# 7-jack-sensor-board-nano.net
KiCad netlist of a schematic drawn in EAGLE
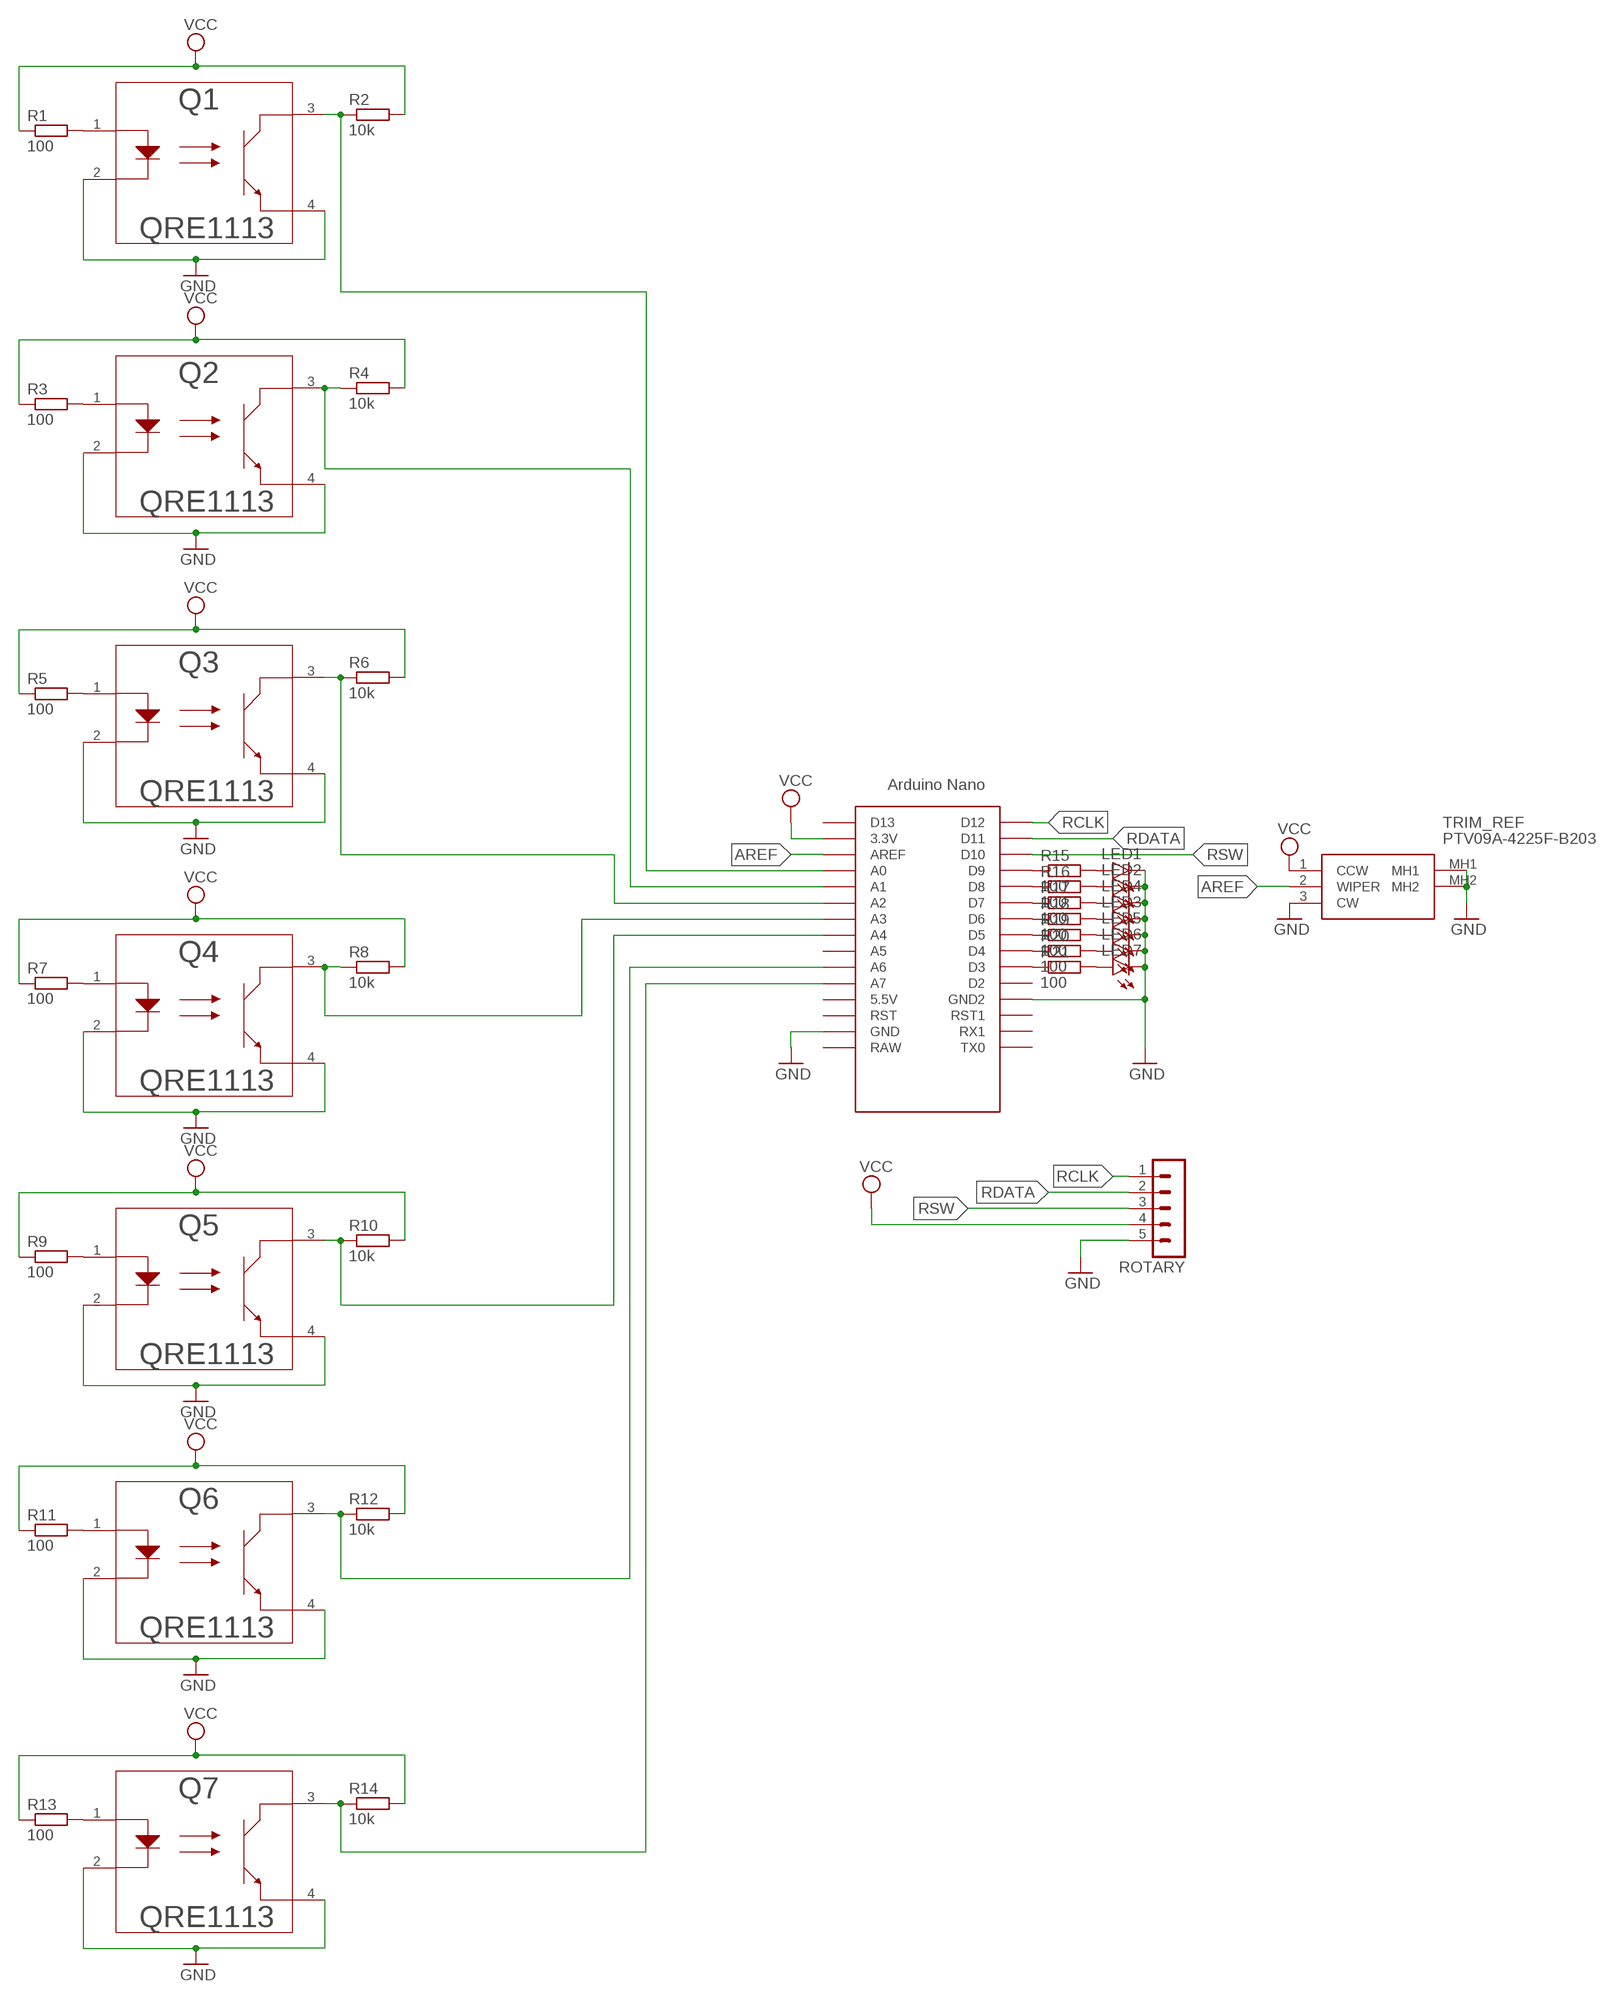
[diagram p0: schematic, sheet 1]

(export (version "E")
  (design (tool "Eeschema 10.0.6"))
  (components
    (comp (ref "LED1")
      (value "LED3MM")
      (footprint "eagle-import:LED3MM")
      (libsource (lib "eagle-import") (part "LED3MM"))
    )
    (comp (ref "LED2")
      (value "LED3MM")
      (footprint "eagle-import:LED3MM")
      (libsource (lib "eagle-import") (part "LED3MM"))
    )
    (comp (ref "LED3")
      (value "LED3MM")
      (footprint "eagle-import:LED3MM")
      (libsource (lib "eagle-import") (part "LED3MM"))
    )
    (comp (ref "LED4")
      (value "LED3MM")
      (footprint "eagle-import:LED3MM")
      (libsource (lib "eagle-import") (part "LED3MM"))
    )
    (comp (ref "LED5")
      (value "LED3MM")
      (footprint "eagle-import:LED3MM")
      (libsource (lib "eagle-import") (part "LED3MM"))
    )
    (comp (ref "LED6")
      (value "LED3MM")
      (footprint "eagle-import:LED3MM")
      (libsource (lib "eagle-import") (part "LED3MM"))
    )
    (comp (ref "LED7")
      (value "LED3MM")
      (footprint "eagle-import:LED3MM")
      (libsource (lib "eagle-import") (part "LED3MM"))
    )
    (comp (ref "Q1")
      (value "QRE1113")
      (footprint "eagle-import:DIP4_100AQ_ONS")
      (fields (field (name "COPYRIGHT") "Copyright (C) 2024 Ultra Librarian. All rights reserved."))
      (libsource (lib "eagle-import") (part "QRE1113"))
    )
    (comp (ref "Q2")
      (value "QRE1113")
      (footprint "eagle-import:DIP4_100AQ_ONS")
      (fields (field (name "COPYRIGHT") "Copyright (C) 2024 Ultra Librarian. All rights reserved."))
      (libsource (lib "eagle-import") (part "QRE1113"))
    )
    (comp (ref "Q3")
      (value "QRE1113")
      (footprint "eagle-import:DIP4_100AQ_ONS")
      (fields (field (name "COPYRIGHT") "Copyright (C) 2024 Ultra Librarian. All rights reserved."))
      (libsource (lib "eagle-import") (part "QRE1113"))
    )
    (comp (ref "Q4")
      (value "QRE1113")
      (footprint "eagle-import:DIP4_100AQ_ONS")
      (fields (field (name "COPYRIGHT") "Copyright (C) 2024 Ultra Librarian. All rights reserved."))
      (libsource (lib "eagle-import") (part "QRE1113"))
    )
    (comp (ref "Q5")
      (value "QRE1113")
      (footprint "eagle-import:DIP4_100AQ_ONS")
      (fields (field (name "COPYRIGHT") "Copyright (C) 2024 Ultra Librarian. All rights reserved."))
      (libsource (lib "eagle-import") (part "QRE1113"))
    )
    (comp (ref "Q6")
      (value "QRE1113")
      (footprint "eagle-import:DIP4_100AQ_ONS")
      (fields (field (name "COPYRIGHT") "Copyright (C) 2024 Ultra Librarian. All rights reserved."))
      (libsource (lib "eagle-import") (part "QRE1113"))
    )
    (comp (ref "Q7")
      (value "QRE1113")
      (footprint "eagle-import:DIP4_100AQ_ONS")
      (fields (field (name "COPYRIGHT") "Copyright (C) 2024 Ultra Librarian. All rights reserved."))
      (libsource (lib "eagle-import") (part "QRE1113"))
    )
    (comp (ref "R1")
      (value "100")
      (footprint "eagle-import:0207_10")
      (libsource (lib "eagle-import") (part "R-EU_0207/10"))
    )
    (comp (ref "R2")
      (value "10k")
      (footprint "eagle-import:0207_10")
      (libsource (lib "eagle-import") (part "R-EU_0207/10"))
    )
    (comp (ref "R3")
      (value "100")
      (footprint "eagle-import:0207_10")
      (libsource (lib "eagle-import") (part "R-EU_0207/10"))
    )
    (comp (ref "R4")
      (value "10k")
      (footprint "eagle-import:0207_10")
      (libsource (lib "eagle-import") (part "R-EU_0207/10"))
    )
    (comp (ref "R5")
      (value "100")
      (footprint "eagle-import:0207_10")
      (libsource (lib "eagle-import") (part "R-EU_0207/10"))
    )
    (comp (ref "R6")
      (value "10k")
      (footprint "eagle-import:0207_10")
      (libsource (lib "eagle-import") (part "R-EU_0207/10"))
    )
    (comp (ref "R7")
      (value "100")
      (footprint "eagle-import:0207_10")
      (libsource (lib "eagle-import") (part "R-EU_0207/10"))
    )
    (comp (ref "R8")
      (value "10k")
      (footprint "eagle-import:0207_10")
      (libsource (lib "eagle-import") (part "R-EU_0207/10"))
    )
    (comp (ref "R9")
      (value "100")
      (footprint "eagle-import:0207_10")
      (libsource (lib "eagle-import") (part "R-EU_0207/10"))
    )
    (comp (ref "R10")
      (value "10k")
      (footprint "eagle-import:0207_10")
      (libsource (lib "eagle-import") (part "R-EU_0207/10"))
    )
    (comp (ref "R11")
      (value "100")
      (footprint "eagle-import:0207_10")
      (libsource (lib "eagle-import") (part "R-EU_0207/10"))
    )
    (comp (ref "R12")
      (value "10k")
      (footprint "eagle-import:0207_10")
      (libsource (lib "eagle-import") (part "R-EU_0207/10"))
    )
    (comp (ref "R13")
      (value "100")
      (footprint "eagle-import:0207_10")
      (libsource (lib "eagle-import") (part "R-EU_0207/10"))
    )
    (comp (ref "R14")
      (value "10k")
      (footprint "eagle-import:0207_10")
      (libsource (lib "eagle-import") (part "R-EU_0207/10"))
    )
    (comp (ref "R15")
      (value "100")
      (footprint "eagle-import:0207_10")
      (libsource (lib "eagle-import") (part "R-EU_0207/10"))
    )
    (comp (ref "R16")
      (value "100")
      (footprint "eagle-import:0207_10")
      (libsource (lib "eagle-import") (part "R-EU_0207/10"))
    )
    (comp (ref "R17")
      (value "100")
      (footprint "eagle-import:0207_10")
      (libsource (lib "eagle-import") (part "R-EU_0207/10"))
    )
    (comp (ref "R18")
      (value "100")
      (footprint "eagle-import:0207_10")
      (libsource (lib "eagle-import") (part "R-EU_0207/10"))
    )
    (comp (ref "R19")
      (value "100")
      (footprint "eagle-import:0207_10")
      (libsource (lib "eagle-import") (part "R-EU_0207/10"))
    )
    (comp (ref "R20")
      (value "100")
      (footprint "eagle-import:0207_10")
      (libsource (lib "eagle-import") (part "R-EU_0207/10"))
    )
    (comp (ref "R21")
      (value "100")
      (footprint "eagle-import:0207_10")
      (libsource (lib "eagle-import") (part "R-EU_0207/10"))
    )
    (comp (ref "ROTARY")
      (value "MA05-1")
      (footprint "eagle-import:MA05-1")
      (libsource (lib "eagle-import") (part "MA05-1"))
    )
    (comp (ref "TRIM_REF")
      (value "PTV09A-4225F-B203")
      (footprint "eagle-import:PTV09A4225FB203")
      (fields (field (name "MOUSER_PART_NUMBER") "652-PTV09A-4225FB203"))
      (libsource (lib "eagle-import") (part "PTV09A-4225F-B203"))
    )
    (comp (ref "U$1")
      (value "NANO")
      (footprint "eagle-import:NANO")
      (libsource (lib "eagle-import") (part "NANO"))
    )
  )
  (nets
    (net (code "1") (name "AREF") (class "Default")
      (node (ref "TRIM_REF") (pin "2") (pinfunction "WIPER_2") (pintype "bidirectional"))
      (node (ref "U$1") (pin "AREF") (pinfunction "AREF_AREF") (pintype "bidirectional"))
    )
    (net (code "2") (name "GND") (class "Default")
      (node (ref "LED1") (pin "K") (pinfunction "C_K") (pintype "passive"))
      (node (ref "LED2") (pin "K") (pinfunction "C_K") (pintype "passive"))
      (node (ref "LED3") (pin "K") (pinfunction "C_K") (pintype "passive"))
      (node (ref "LED4") (pin "K") (pinfunction "C_K") (pintype "passive"))
      (node (ref "LED5") (pin "K") (pinfunction "C_K") (pintype "passive"))
      (node (ref "LED6") (pin "K") (pinfunction "C_K") (pintype "passive"))
      (node (ref "LED7") (pin "K") (pinfunction "C_K") (pintype "passive"))
      (node (ref "Q1") (pin "2") (pinfunction "2_2") (pintype "passive"))
      (node (ref "Q1") (pin "4") (pinfunction "4_4") (pintype "passive"))
      (node (ref "Q2") (pin "2") (pinfunction "2_2") (pintype "passive"))
      (node (ref "Q2") (pin "4") (pinfunction "4_4") (pintype "passive"))
      (node (ref "Q3") (pin "2") (pinfunction "2_2") (pintype "passive"))
      (node (ref "Q3") (pin "4") (pinfunction "4_4") (pintype "passive"))
      (node (ref "Q4") (pin "2") (pinfunction "2_2") (pintype "passive"))
      (node (ref "Q4") (pin "4") (pinfunction "4_4") (pintype "passive"))
      (node (ref "Q5") (pin "2") (pinfunction "2_2") (pintype "passive"))
      (node (ref "Q5") (pin "4") (pinfunction "4_4") (pintype "passive"))
      (node (ref "Q6") (pin "2") (pinfunction "2_2") (pintype "passive"))
      (node (ref "Q6") (pin "4") (pinfunction "4_4") (pintype "passive"))
      (node (ref "Q7") (pin "2") (pinfunction "2_2") (pintype "passive"))
      (node (ref "Q7") (pin "4") (pinfunction "4_4") (pintype "passive"))
      (node (ref "ROTARY") (pin "5") (pinfunction "5_5") (pintype "passive"))
      (node (ref "TRIM_REF") (pin "3") (pinfunction "CW_3") (pintype "bidirectional"))
      (node (ref "TRIM_REF") (pin "MH1") (pinfunction "MH1_MH1") (pintype "bidirectional"))
      (node (ref "TRIM_REF") (pin "MH2") (pinfunction "MH2_MH2") (pintype "bidirectional"))
      (node (ref "U$1") (pin "GND") (pinfunction "GND_GND") (pintype "bidirectional"))
      (node (ref "U$1") (pin "GND1") (pinfunction "GND2_GND1") (pintype "bidirectional"))
    )
    (net (code "3") (name "Net-(LED1-PadA)") (class "Default")
      (node (ref "LED1") (pin "A") (pinfunction "A_A") (pintype "passive"))
      (node (ref "R15") (pin "2") (pinfunction "2_2") (pintype "passive"))
    )
    (net (code "4") (name "Net-(LED2-PadA)") (class "Default")
      (node (ref "LED2") (pin "A") (pinfunction "A_A") (pintype "passive"))
      (node (ref "R16") (pin "2") (pinfunction "2_2") (pintype "passive"))
    )
    (net (code "5") (name "Net-(LED3-PadA)") (class "Default")
      (node (ref "LED3") (pin "A") (pinfunction "A_A") (pintype "passive"))
      (node (ref "R18") (pin "2") (pinfunction "2_2") (pintype "passive"))
    )
    (net (code "6") (name "Net-(LED4-PadA)") (class "Default")
      (node (ref "LED4") (pin "A") (pinfunction "A_A") (pintype "passive"))
      (node (ref "R17") (pin "2") (pinfunction "2_2") (pintype "passive"))
    )
    (net (code "7") (name "Net-(LED5-PadA)") (class "Default")
      (node (ref "LED5") (pin "A") (pinfunction "A_A") (pintype "passive"))
      (node (ref "R19") (pin "2") (pinfunction "2_2") (pintype "passive"))
    )
    (net (code "8") (name "Net-(LED6-PadA)") (class "Default")
      (node (ref "LED6") (pin "A") (pinfunction "A_A") (pintype "passive"))
      (node (ref "R20") (pin "2") (pinfunction "2_2") (pintype "passive"))
    )
    (net (code "9") (name "Net-(LED7-PadA)") (class "Default")
      (node (ref "LED7") (pin "A") (pinfunction "A_A") (pintype "passive"))
      (node (ref "R21") (pin "2") (pinfunction "2_2") (pintype "passive"))
    )
    (net (code "10") (name "Net-(Q1-Pad1)") (class "Default")
      (node (ref "Q1") (pin "1") (pinfunction "1_1") (pintype "passive"))
      (node (ref "R1") (pin "2") (pinfunction "2_2") (pintype "passive"))
    )
    (net (code "11") (name "Net-(Q1-Pad3)") (class "Default")
      (node (ref "Q1") (pin "3") (pinfunction "3_3") (pintype "passive"))
      (node (ref "R2") (pin "1") (pinfunction "1_1") (pintype "passive"))
      (node (ref "U$1") (pin "A0") (pinfunction "A0_A0") (pintype "bidirectional"))
    )
    (net (code "12") (name "Net-(Q2-Pad1)") (class "Default")
      (node (ref "Q2") (pin "1") (pinfunction "1_1") (pintype "passive"))
      (node (ref "R3") (pin "2") (pinfunction "2_2") (pintype "passive"))
    )
    (net (code "13") (name "Net-(Q2-Pad3)") (class "Default")
      (node (ref "Q2") (pin "3") (pinfunction "3_3") (pintype "passive"))
      (node (ref "R4") (pin "1") (pinfunction "1_1") (pintype "passive"))
      (node (ref "U$1") (pin "A1") (pinfunction "A1_A1") (pintype "bidirectional"))
    )
    (net (code "14") (name "Net-(Q3-Pad1)") (class "Default")
      (node (ref "Q3") (pin "1") (pinfunction "1_1") (pintype "passive"))
      (node (ref "R5") (pin "2") (pinfunction "2_2") (pintype "passive"))
    )
    (net (code "15") (name "Net-(Q3-Pad3)") (class "Default")
      (node (ref "Q3") (pin "3") (pinfunction "3_3") (pintype "passive"))
      (node (ref "R6") (pin "1") (pinfunction "1_1") (pintype "passive"))
      (node (ref "U$1") (pin "A2") (pinfunction "A2_A2") (pintype "bidirectional"))
    )
    (net (code "16") (name "Net-(Q4-Pad1)") (class "Default")
      (node (ref "Q4") (pin "1") (pinfunction "1_1") (pintype "passive"))
      (node (ref "R7") (pin "2") (pinfunction "2_2") (pintype "passive"))
    )
    (net (code "17") (name "Net-(Q4-Pad3)") (class "Default")
      (node (ref "Q4") (pin "3") (pinfunction "3_3") (pintype "passive"))
      (node (ref "R8") (pin "1") (pinfunction "1_1") (pintype "passive"))
      (node (ref "U$1") (pin "A3") (pinfunction "A3_A3") (pintype "bidirectional"))
    )
    (net (code "18") (name "Net-(Q5-Pad1)") (class "Default")
      (node (ref "Q5") (pin "1") (pinfunction "1_1") (pintype "passive"))
      (node (ref "R9") (pin "2") (pinfunction "2_2") (pintype "passive"))
    )
    (net (code "19") (name "Net-(Q5-Pad3)") (class "Default")
      (node (ref "Q5") (pin "3") (pinfunction "3_3") (pintype "passive"))
      (node (ref "R10") (pin "1") (pinfunction "1_1") (pintype "passive"))
      (node (ref "U$1") (pin "A4") (pinfunction "A4_A4") (pintype "bidirectional"))
    )
    (net (code "20") (name "Net-(Q6-Pad1)") (class "Default")
      (node (ref "Q6") (pin "1") (pinfunction "1_1") (pintype "passive"))
      (node (ref "R11") (pin "2") (pinfunction "2_2") (pintype "passive"))
    )
    (net (code "21") (name "Net-(Q6-Pad3)") (class "Default")
      (node (ref "Q6") (pin "3") (pinfunction "3_3") (pintype "passive"))
      (node (ref "R12") (pin "1") (pinfunction "1_1") (pintype "passive"))
      (node (ref "U$1") (pin "A6") (pinfunction "A6_A6") (pintype "bidirectional"))
    )
    (net (code "22") (name "Net-(Q7-Pad1)") (class "Default")
      (node (ref "Q7") (pin "1") (pinfunction "1_1") (pintype "passive"))
      (node (ref "R13") (pin "2") (pinfunction "2_2") (pintype "passive"))
    )
    (net (code "23") (name "Net-(Q7-Pad3)") (class "Default")
      (node (ref "Q7") (pin "3") (pinfunction "3_3") (pintype "passive"))
      (node (ref "R14") (pin "1") (pinfunction "1_1") (pintype "passive"))
      (node (ref "U$1") (pin "A7") (pinfunction "A7_A7") (pintype "bidirectional"))
    )
    (net (code "24") (name "Net-(R15-Pad1)") (class "Default")
      (node (ref "R15") (pin "1") (pinfunction "1_1") (pintype "passive"))
      (node (ref "U$1") (pin "D9") (pinfunction "D9_D9") (pintype "bidirectional"))
    )
    (net (code "25") (name "Net-(R16-Pad1)") (class "Default")
      (node (ref "R16") (pin "1") (pinfunction "1_1") (pintype "passive"))
      (node (ref "U$1") (pin "D8") (pinfunction "D8_D8") (pintype "bidirectional"))
    )
    (net (code "26") (name "Net-(R17-Pad1)") (class "Default")
      (node (ref "R17") (pin "1") (pinfunction "1_1") (pintype "passive"))
      (node (ref "U$1") (pin "D7") (pinfunction "D7_D7") (pintype "bidirectional"))
    )
    (net (code "27") (name "Net-(R18-Pad1)") (class "Default")
      (node (ref "R18") (pin "1") (pinfunction "1_1") (pintype "passive"))
      (node (ref "U$1") (pin "D6") (pinfunction "D6_D6") (pintype "bidirectional"))
    )
    (net (code "28") (name "Net-(R19-Pad1)") (class "Default")
      (node (ref "R19") (pin "1") (pinfunction "1_1") (pintype "passive"))
      (node (ref "U$1") (pin "D5") (pinfunction "D5_D5") (pintype "bidirectional"))
    )
    (net (code "29") (name "Net-(R20-Pad1)") (class "Default")
      (node (ref "R20") (pin "1") (pinfunction "1_1") (pintype "passive"))
      (node (ref "U$1") (pin "D4") (pinfunction "D4_D4") (pintype "bidirectional"))
    )
    (net (code "30") (name "Net-(R21-Pad1)") (class "Default")
      (node (ref "R21") (pin "1") (pinfunction "1_1") (pintype "passive"))
      (node (ref "U$1") (pin "D3") (pinfunction "D3_D3") (pintype "bidirectional"))
    )
    (net (code "31") (name "RCLK") (class "Default")
      (node (ref "ROTARY") (pin "1") (pinfunction "1_1") (pintype "passive"))
      (node (ref "U$1") (pin "D12") (pinfunction "D12_D12") (pintype "bidirectional"))
    )
    (net (code "32") (name "RDATA") (class "Default")
      (node (ref "ROTARY") (pin "2") (pinfunction "2_2") (pintype "passive"))
      (node (ref "U$1") (pin "D11") (pinfunction "D11_D11") (pintype "bidirectional"))
    )
    (net (code "33") (name "RSW") (class "Default")
      (node (ref "ROTARY") (pin "3") (pinfunction "3_3") (pintype "passive"))
      (node (ref "U$1") (pin "D10") (pinfunction "D10_D10") (pintype "bidirectional"))
    )
    (net (code "34") (name "VCC") (class "Default")
      (node (ref "R1") (pin "1") (pinfunction "1_1") (pintype "passive"))
      (node (ref "R10") (pin "2") (pinfunction "2_2") (pintype "passive"))
      (node (ref "R11") (pin "1") (pinfunction "1_1") (pintype "passive"))
      (node (ref "R12") (pin "2") (pinfunction "2_2") (pintype "passive"))
      (node (ref "R13") (pin "1") (pinfunction "1_1") (pintype "passive"))
      (node (ref "R14") (pin "2") (pinfunction "2_2") (pintype "passive"))
      (node (ref "R2") (pin "2") (pinfunction "2_2") (pintype "passive"))
      (node (ref "R3") (pin "1") (pinfunction "1_1") (pintype "passive"))
      (node (ref "R4") (pin "2") (pinfunction "2_2") (pintype "passive"))
      (node (ref "R5") (pin "1") (pinfunction "1_1") (pintype "passive"))
      (node (ref "R6") (pin "2") (pinfunction "2_2") (pintype "passive"))
      (node (ref "R7") (pin "1") (pinfunction "1_1") (pintype "passive"))
      (node (ref "R8") (pin "2") (pinfunction "2_2") (pintype "passive"))
      (node (ref "R9") (pin "1") (pinfunction "1_1") (pintype "passive"))
      (node (ref "ROTARY") (pin "4") (pinfunction "4_4") (pintype "passive"))
      (node (ref "TRIM_REF") (pin "1") (pinfunction "CCW_1") (pintype "bidirectional"))
      (node (ref "U$1") (pin "3.3V") (pinfunction "3.3V_3.3V") (pintype "bidirectional"))
    )
    (net (code "35") (name "unconnected-(U$1-5.5V-Pad5V)") (class "Default")
      (node (ref "U$1") (pin "5V") (pinfunction "5.5V_5V") (pintype "bidirectional"))
    )
    (net (code "36") (name "unconnected-(U$1-PadA5)") (class "Default")
      (node (ref "U$1") (pin "A5") (pinfunction "A5_A5") (pintype "bidirectional"))
    )
    (net (code "37") (name "unconnected-(U$1-PadD2)") (class "Default")
      (node (ref "U$1") (pin "D2") (pinfunction "D2_D2") (pintype "bidirectional"))
    )
    (net (code "38") (name "unconnected-(U$1-PadD13)") (class "Default")
      (node (ref "U$1") (pin "D13") (pinfunction "D13_D13") (pintype "bidirectional"))
    )
    (net (code "39") (name "unconnected-(U$1-PadICSP1)") (class "Default")
      (node (ref "U$1") (pin "ICSP1") (pinfunction "ICSP1_ICSP1") (pintype "bidirectional"))
    )
    (net (code "40") (name "unconnected-(U$1-PadICSP2)") (class "Default")
      (node (ref "U$1") (pin "ICSP2") (pinfunction "ICSP2_ICSP2") (pintype "bidirectional"))
    )
    (net (code "41") (name "unconnected-(U$1-PadICSP3)") (class "Default")
      (node (ref "U$1") (pin "ICSP3") (pinfunction "ICSP3_ICSP3") (pintype "bidirectional"))
    )
    (net (code "42") (name "unconnected-(U$1-PadICSP4)") (class "Default")
      (node (ref "U$1") (pin "ICSP4") (pinfunction "ICSP4_ICSP4") (pintype "bidirectional"))
    )
    (net (code "43") (name "unconnected-(U$1-PadICSP5)") (class "Default")
      (node (ref "U$1") (pin "ICSP5") (pinfunction "ICSP5_ICSP5") (pintype "bidirectional"))
    )
    (net (code "44") (name "unconnected-(U$1-PadICSP6)") (class "Default")
      (node (ref "U$1") (pin "ICSP6") (pinfunction "ICSP6_ICSP6") (pintype "bidirectional"))
    )
    (net (code "45") (name "unconnected-(U$1-PadRAW)") (class "Default")
      (node (ref "U$1") (pin "RAW") (pinfunction "RAW_RAW") (pintype "bidirectional"))
    )
    (net (code "46") (name "unconnected-(U$1-PadRST)") (class "Default")
      (node (ref "U$1") (pin "RST") (pinfunction "RST_RST") (pintype "bidirectional"))
    )
    (net (code "47") (name "unconnected-(U$1-PadRST1)") (class "Default")
      (node (ref "U$1") (pin "RST1") (pinfunction "RST1_RST1") (pintype "bidirectional"))
    )
    (net (code "48") (name "unconnected-(U$1-PadRX1)") (class "Default")
      (node (ref "U$1") (pin "RX1") (pinfunction "RX1_RX1") (pintype "bidirectional"))
    )
    (net (code "49") (name "unconnected-(U$1-PadTX0)") (class "Default")
      (node (ref "U$1") (pin "TX0") (pinfunction "TX0_TX0") (pintype "bidirectional"))
    )
  )
)
